# Roboteq_Board_V1_1.net
KiCad netlist of a schematic drawn in EAGLE
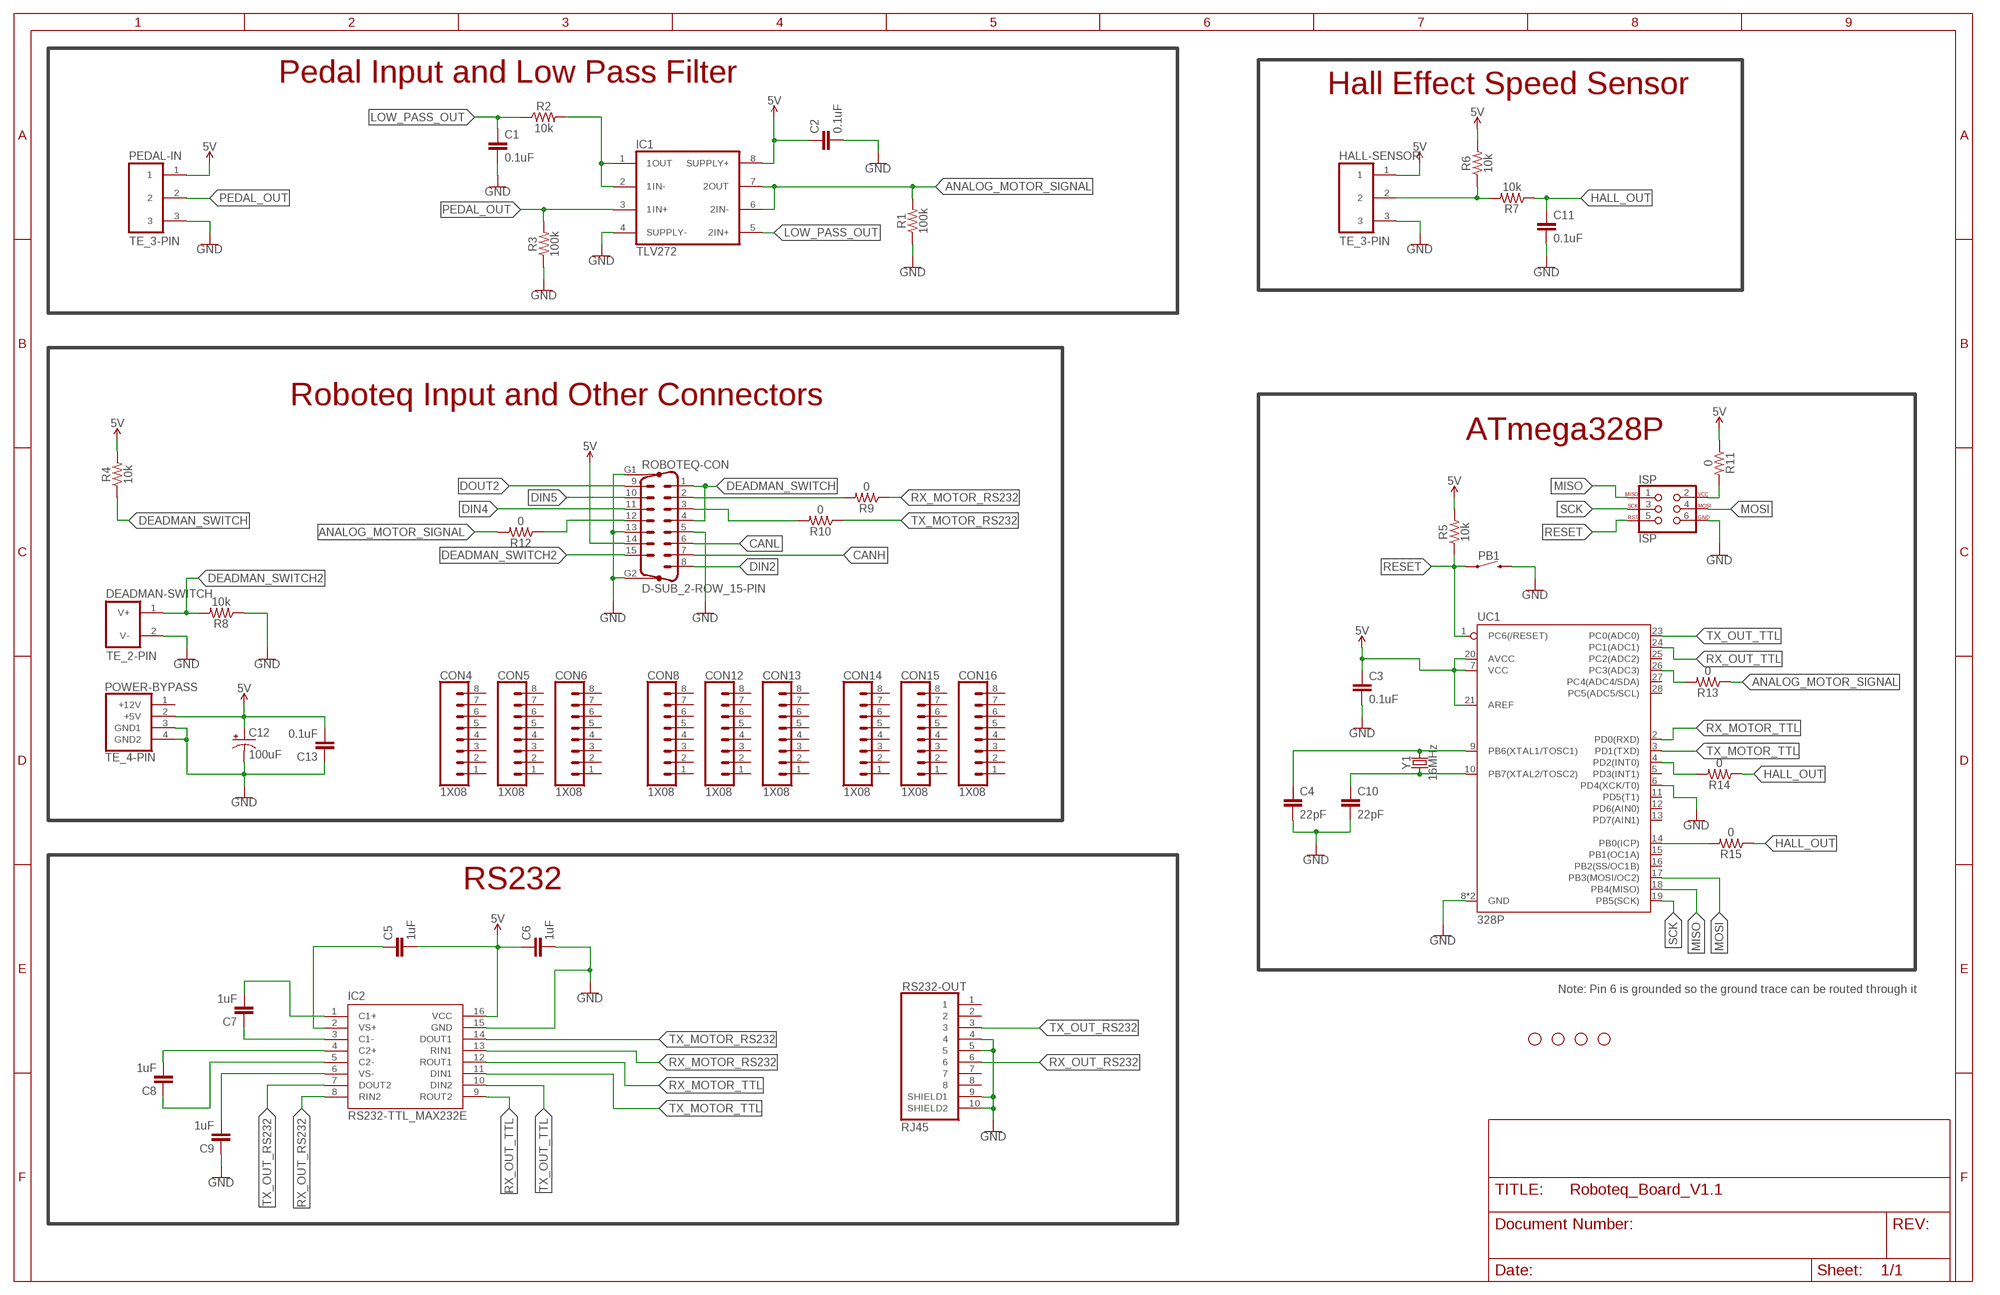
[diagram p0: schematic, sheet 1]

(export (version "E")
  (design (tool "Eeschema 10.0.6"))
  (components
    (comp (ref "C1")
      (value "0.1uF")
      (footprint "eagle-import:CAP-PTH-5MM")
      (libsource (lib "eagle-import") (part "CAPACITOR_CERAMIC_THROUGH-HOLE"))
    )
    (comp (ref "C2")
      (value "0.1uF")
      (footprint "eagle-import:CAP-PTH-5MM")
      (libsource (lib "eagle-import") (part "CAPACITOR_CERAMIC_THROUGH-HOLE"))
    )
    (comp (ref "C3")
      (value "0.1uF")
      (footprint "eagle-import:CAP-PTH-5MM")
      (libsource (lib "eagle-import") (part "CAPACITOR_CERAMIC_THROUGH-HOLE"))
    )
    (comp (ref "C4")
      (value "22pF")
      (footprint "eagle-import:CAP-PTH-5MM")
      (libsource (lib "eagle-import") (part "CAPACITOR_CERAMIC_THROUGH-HOLE"))
    )
    (comp (ref "C5")
      (value "1uF")
      (footprint "eagle-import:CAP-PTH-5MM")
      (libsource (lib "eagle-import") (part "CAPACITOR_CERAMIC_THROUGH-HOLE"))
    )
    (comp (ref "C6")
      (value "1uF")
      (footprint "eagle-import:CAP-PTH-5MM")
      (libsource (lib "eagle-import") (part "CAPACITOR_CERAMIC_THROUGH-HOLE"))
    )
    (comp (ref "C7")
      (value "1uF")
      (footprint "eagle-import:CAP-PTH-5MM")
      (libsource (lib "eagle-import") (part "CAPACITOR_CERAMIC_THROUGH-HOLE"))
    )
    (comp (ref "C8")
      (value "1uF")
      (footprint "eagle-import:CAP-PTH-5MM")
      (libsource (lib "eagle-import") (part "CAPACITOR_CERAMIC_THROUGH-HOLE"))
    )
    (comp (ref "C9")
      (value "1uF")
      (footprint "eagle-import:CAP-PTH-5MM")
      (libsource (lib "eagle-import") (part "CAPACITOR_CERAMIC_THROUGH-HOLE"))
    )
    (comp (ref "C10")
      (value "22pF")
      (footprint "eagle-import:CAP-PTH-5MM")
      (libsource (lib "eagle-import") (part "CAPACITOR_CERAMIC_THROUGH-HOLE"))
    )
    (comp (ref "C11")
      (value "0.1uF")
      (footprint "eagle-import:CAP-PTH-5MM")
      (libsource (lib "eagle-import") (part "CAPACITOR_CERAMIC_THROUGH-HOLE"))
    )
    (comp (ref "C12")
      (value "100uF")
      (footprint "eagle-import:CAPACITOR_100UF_50V")
      (libsource (lib "eagle-import") (part "CAPACITOR_ELECTROLYTIC_100UF"))
    )
    (comp (ref "C13")
      (value "0.1uF")
      (footprint "eagle-import:CAP-PTH-5MM")
      (libsource (lib "eagle-import") (part "CAPACITOR_CERAMIC_THROUGH-HOLE"))
    )
    (comp (ref "CON4")
      (value "1X08")
      (footprint "eagle-import:1X08")
      (libsource (lib "eagle-import") (part "1X08"))
    )
    (comp (ref "CON5")
      (value "1X08")
      (footprint "eagle-import:1X08")
      (libsource (lib "eagle-import") (part "1X08"))
    )
    (comp (ref "CON6")
      (value "1X08")
      (footprint "eagle-import:1X08")
      (libsource (lib "eagle-import") (part "1X08"))
    )
    (comp (ref "CON8")
      (value "1X08")
      (footprint "eagle-import:1X08")
      (libsource (lib "eagle-import") (part "1X08"))
    )
    (comp (ref "CON12")
      (value "1X08")
      (footprint "eagle-import:1X08")
      (libsource (lib "eagle-import") (part "1X08"))
    )
    (comp (ref "CON13")
      (value "1X08")
      (footprint "eagle-import:1X08")
      (libsource (lib "eagle-import") (part "1X08"))
    )
    (comp (ref "CON14")
      (value "1X08")
      (footprint "eagle-import:1X08")
      (libsource (lib "eagle-import") (part "1X08"))
    )
    (comp (ref "CON15")
      (value "1X08")
      (footprint "eagle-import:1X08")
      (libsource (lib "eagle-import") (part "1X08"))
    )
    (comp (ref "CON16")
      (value "1X08")
      (footprint "eagle-import:1X08")
      (libsource (lib "eagle-import") (part "1X08"))
    )
    (comp (ref "DEADMAN-SWITCH")
      (value "TE_2-PIN")
      (footprint "eagle-import:TE_2-PIN")
      (libsource (lib "eagle-import") (part "TE_2-PIN"))
    )
    (comp (ref "H1")
      (value "STAND-OFF")
      (footprint "eagle-import:STAND-OFF")
      (libsource (lib "eagle-import") (part "STAND-OFF"))
    )
    (comp (ref "H2")
      (value "STAND-OFF")
      (footprint "eagle-import:STAND-OFF")
      (libsource (lib "eagle-import") (part "STAND-OFF"))
    )
    (comp (ref "H3")
      (value "STAND-OFF")
      (footprint "eagle-import:STAND-OFF")
      (libsource (lib "eagle-import") (part "STAND-OFF"))
    )
    (comp (ref "H4")
      (value "STAND-OFF")
      (footprint "eagle-import:STAND-OFF")
      (libsource (lib "eagle-import") (part "STAND-OFF"))
    )
    (comp (ref "HALL-SENSOR")
      (value "TE_3-PIN")
      (footprint "eagle-import:TE_3-PIN")
      (libsource (lib "eagle-import") (part "TE_3-PIN"))
    )
    (comp (ref "IC1")
      (value "TLV272")
      (footprint "eagle-import:DIP08")
      (libsource (lib "eagle-import") (part "OP-AMP_DUAL"))
    )
    (comp (ref "IC2")
      (value "RS232-TTL_MAX232E")
      (footprint "eagle-import:DIP16")
      (libsource (lib "eagle-import") (part "RS232-TTL_MAX232E"))
    )
    (comp (ref "ISP")
      (value "ISP")
      (footprint "eagle-import:ISP_CONNECTOR")
      (libsource (lib "eagle-import") (part "ISP"))
    )
    (comp (ref "PB1")
      (value "PUSHBUTTON")
      (footprint "eagle-import:PUSHBUTTON")
      (libsource (lib "eagle-import") (part "PUSHBUTTON"))
    )
    (comp (ref "PEDAL-IN")
      (value "TE_3-PIN")
      (footprint "eagle-import:TE_3-PIN")
      (libsource (lib "eagle-import") (part "TE_3-PIN"))
    )
    (comp (ref "POWER-BYPASS")
      (value "TE_4-PIN")
      (footprint "eagle-import:TE_4-PIN")
      (libsource (lib "eagle-import") (part "TE_4-PIN"))
    )
    (comp (ref "R1")
      (value "100k")
      (footprint "eagle-import:AXIAL-0.3")
      (libsource (lib "eagle-import") (part "RESISTOR_THROUGH-HOLE_1/4W"))
    )
    (comp (ref "R2")
      (value "10k")
      (footprint "eagle-import:AXIAL-0.3")
      (libsource (lib "eagle-import") (part "RESISTOR_THROUGH-HOLE_1/4W"))
    )
    (comp (ref "R3")
      (value "100k")
      (footprint "eagle-import:AXIAL-0.3")
      (libsource (lib "eagle-import") (part "RESISTOR_THROUGH-HOLE_1/4W"))
    )
    (comp (ref "R4")
      (value "10k")
      (footprint "eagle-import:AXIAL-0.3")
      (libsource (lib "eagle-import") (part "RESISTOR_THROUGH-HOLE_1/4W"))
    )
    (comp (ref "R5")
      (value "10k")
      (footprint "eagle-import:AXIAL-0.3")
      (libsource (lib "eagle-import") (part "RESISTOR_THROUGH-HOLE_1/4W"))
    )
    (comp (ref "R6")
      (value "10k")
      (footprint "eagle-import:AXIAL-0.3")
      (libsource (lib "eagle-import") (part "RESISTOR_THROUGH-HOLE_1/4W"))
    )
    (comp (ref "R7")
      (value "10k")
      (footprint "eagle-import:AXIAL-0.3")
      (libsource (lib "eagle-import") (part "RESISTOR_THROUGH-HOLE_1/4W"))
    )
    (comp (ref "R8")
      (value "10k")
      (footprint "eagle-import:AXIAL-0.3")
      (libsource (lib "eagle-import") (part "RESISTOR_THROUGH-HOLE_1/4W"))
    )
    (comp (ref "R9")
      (value "0")
      (footprint "eagle-import:AXIAL-0.3")
      (libsource (lib "eagle-import") (part "RESISTOR_THROUGH-HOLE_1/4W"))
    )
    (comp (ref "R10")
      (value "0")
      (footprint "eagle-import:AXIAL-0.3")
      (libsource (lib "eagle-import") (part "RESISTOR_THROUGH-HOLE_1/4W"))
    )
    (comp (ref "R11")
      (value "0")
      (footprint "eagle-import:AXIAL-0.3")
      (libsource (lib "eagle-import") (part "RESISTOR_THROUGH-HOLE_1/4W"))
    )
    (comp (ref "R12")
      (value "0")
      (footprint "eagle-import:AXIAL-0.3")
      (libsource (lib "eagle-import") (part "RESISTOR_THROUGH-HOLE_1/4W"))
    )
    (comp (ref "R13")
      (value "0")
      (footprint "eagle-import:AXIAL-0.3")
      (libsource (lib "eagle-import") (part "RESISTOR_THROUGH-HOLE_1/4W"))
    )
    (comp (ref "R14")
      (value "0")
      (footprint "eagle-import:AXIAL-0.3")
      (libsource (lib "eagle-import") (part "RESISTOR_THROUGH-HOLE_1/4W"))
    )
    (comp (ref "R15")
      (value "0")
      (footprint "eagle-import:AXIAL-0.3")
      (libsource (lib "eagle-import") (part "RESISTOR_THROUGH-HOLE_1/4W"))
    )
    (comp (ref "ROBOTEQ-CON")
      (value "D-SUB_2-ROW_15-PIN")
      (footprint "eagle-import:D-SUB_2-ROW_15-PIN")
      (libsource (lib "eagle-import") (part "D-SUB_2-ROW_15-PIN"))
    )
    (comp (ref "RS232-OUT")
      (value "RJ45")
      (footprint "eagle-import:RJ45")
      (libsource (lib "eagle-import") (part "RJ45"))
    )
    (comp (ref "UC1")
      (value "328P")
      (footprint "eagle-import:DIP28")
      (libsource (lib "eagle-import") (part "ATMEGA328P_DIP28"))
    )
    (comp (ref "Y1")
      (value "16MHz")
      (footprint "eagle-import:HC49US")
      (libsource (lib "eagle-import") (part "CRYSTAL-16MHZPTH-HC49US"))
    )
  )
  (nets
    (net (code "1") (name "5V") (class "Default")
      (node (ref "C12") (pin "+") (pinfunction "+_+") (pintype "passive"))
      (node (ref "C13") (pin "2") (pinfunction "2_2") (pintype "passive"))
      (node (ref "C2") (pin "1") (pinfunction "1_1") (pintype "passive"))
      (node (ref "C3") (pin "1") (pinfunction "1_1") (pintype "passive"))
      (node (ref "C5") (pin "2") (pinfunction "2_2") (pintype "passive"))
      (node (ref "C6") (pin "1") (pinfunction "1_1") (pintype "passive"))
      (node (ref "HALL-SENSOR") (pin "1") (pinfunction "1_1") (pintype "passive"))
      (node (ref "IC1") (pin "8") (pinfunction "SUPPLY+_8") (pintype "bidirectional"))
      (node (ref "IC2") (pin "16") (pinfunction "VCC_16") (pintype "bidirectional"))
      (node (ref "PEDAL-IN") (pin "1") (pinfunction "1_1") (pintype "passive"))
      (node (ref "POWER-BYPASS") (pin "2") (pinfunction "+5V_2") (pintype "passive"))
      (node (ref "R11") (pin "P$1") (pinfunction "1_P$1") (pintype "passive"))
      (node (ref "R4") (pin "P$2") (pinfunction "2_P$2") (pintype "passive"))
      (node (ref "R5") (pin "P$2") (pinfunction "2_P$2") (pintype "passive"))
      (node (ref "R6") (pin "P$2") (pinfunction "2_P$2") (pintype "passive"))
      (node (ref "ROBOTEQ-CON") (pin "14") (pinfunction "14_14") (pintype "passive"))
      (node (ref "UC1") (pin "20") (pinfunction "AVCC_20") (pintype "bidirectional"))
      (node (ref "UC1") (pin "21") (pinfunction "AREF_21") (pintype "bidirectional"))
      (node (ref "UC1") (pin "7") (pinfunction "VCC_7") (pintype "bidirectional"))
    )
    (net (code "2") (name "ANALOG_MOTOR_SIGNAL") (class "Default")
      (node (ref "IC1") (pin "6") (pinfunction "2IN-_6") (pintype "bidirectional"))
      (node (ref "IC1") (pin "7") (pinfunction "2OUT_7") (pintype "bidirectional"))
      (node (ref "R1") (pin "P$2") (pinfunction "2_P$2") (pintype "passive"))
      (node (ref "R12") (pin "P$2") (pinfunction "2_P$2") (pintype "passive"))
      (node (ref "R13") (pin "P$1") (pinfunction "1_P$1") (pintype "passive"))
    )
    (net (code "3") (name "CANH") (class "Default")
      (node (ref "ROBOTEQ-CON") (pin "7") (pinfunction "7_7") (pintype "passive"))
    )
    (net (code "4") (name "CANL") (class "Default")
      (node (ref "ROBOTEQ-CON") (pin "6") (pinfunction "6_6") (pintype "passive"))
    )
    (net (code "5") (name "DEADMAN_SWITCH") (class "Default")
      (node (ref "R4") (pin "P$1") (pinfunction "1_P$1") (pintype "passive"))
      (node (ref "ROBOTEQ-CON") (pin "1") (pinfunction "1_1") (pintype "passive"))
      (node (ref "ROBOTEQ-CON") (pin "4") (pinfunction "4_4") (pintype "passive"))
    )
    (net (code "6") (name "DEADMAN_SWITCH2") (class "Default")
      (node (ref "DEADMAN-SWITCH") (pin "1") (pinfunction "V+_1") (pintype "passive"))
      (node (ref "R8") (pin "P$2") (pinfunction "2_P$2") (pintype "passive"))
      (node (ref "ROBOTEQ-CON") (pin "15") (pinfunction "15_15") (pintype "passive"))
    )
    (net (code "7") (name "DIN2") (class "Default")
      (node (ref "ROBOTEQ-CON") (pin "8") (pinfunction "8_8") (pintype "passive"))
    )
    (net (code "8") (name "DIN4") (class "Default")
      (node (ref "ROBOTEQ-CON") (pin "11") (pinfunction "11_11") (pintype "passive"))
    )
    (net (code "9") (name "DIN5") (class "Default")
      (node (ref "ROBOTEQ-CON") (pin "10") (pinfunction "10_10") (pintype "passive"))
    )
    (net (code "10") (name "DOUT2") (class "Default")
      (node (ref "ROBOTEQ-CON") (pin "9") (pinfunction "9_9") (pintype "passive"))
    )
    (net (code "11") (name "GND") (class "Default")
      (node (ref "C1") (pin "2") (pinfunction "2_2") (pintype "passive"))
      (node (ref "C10") (pin "2") (pinfunction "2_2") (pintype "passive"))
      (node (ref "C11") (pin "2") (pinfunction "2_2") (pintype "passive"))
      (node (ref "C12") (pin "-") (pinfunction "-_-") (pintype "passive"))
      (node (ref "C13") (pin "1") (pinfunction "1_1") (pintype "passive"))
      (node (ref "C2") (pin "2") (pinfunction "2_2") (pintype "passive"))
      (node (ref "C3") (pin "2") (pinfunction "2_2") (pintype "passive"))
      (node (ref "C4") (pin "2") (pinfunction "2_2") (pintype "passive"))
      (node (ref "C6") (pin "2") (pinfunction "2_2") (pintype "passive"))
      (node (ref "C9") (pin "1") (pinfunction "1_1") (pintype "passive"))
      (node (ref "DEADMAN-SWITCH") (pin "2") (pinfunction "V-_2") (pintype "passive"))
      (node (ref "HALL-SENSOR") (pin "3") (pinfunction "3_3") (pintype "passive"))
      (node (ref "IC1") (pin "4") (pinfunction "SUPPLY-_4") (pintype "bidirectional"))
      (node (ref "IC2") (pin "15") (pinfunction "GND_15") (pintype "bidirectional"))
      (node (ref "ISP") (pin "6") (pinfunction "6_6") (pintype "passive"))
      (node (ref "PB1") (pin "3") (pinfunction "2_3") (pintype "passive"))
      (node (ref "PB1") (pin "4") (pinfunction "2_4") (pintype "passive"))
      (node (ref "PEDAL-IN") (pin "3") (pinfunction "3_3") (pintype "passive"))
      (node (ref "POWER-BYPASS") (pin "3") (pinfunction "GND1_3") (pintype "passive"))
      (node (ref "POWER-BYPASS") (pin "4") (pinfunction "GND2_4") (pintype "passive"))
      (node (ref "R1") (pin "P$1") (pinfunction "1_P$1") (pintype "passive"))
      (node (ref "R3") (pin "P$1") (pinfunction "1_P$1") (pintype "passive"))
      (node (ref "R8") (pin "P$1") (pinfunction "1_P$1") (pintype "passive"))
      (node (ref "ROBOTEQ-CON") (pin "13") (pinfunction "13_13") (pintype "passive"))
      (node (ref "ROBOTEQ-CON") (pin "5") (pinfunction "5_5") (pintype "passive"))
      (node (ref "ROBOTEQ-CON") (pin "G1") (pinfunction "GND1_G1") (pintype "passive"))
      (node (ref "ROBOTEQ-CON") (pin "G2") (pinfunction "GND2_G2") (pintype "passive"))
      (node (ref "RS232-OUT") (pin "10") (pinfunction "SHIELD2_10") (pintype "passive"))
      (node (ref "RS232-OUT") (pin "4") (pinfunction "4_4") (pintype "passive"))
      (node (ref "RS232-OUT") (pin "5") (pinfunction "5_5") (pintype "passive"))
      (node (ref "RS232-OUT") (pin "9") (pinfunction "SHIELD1_9") (pintype "passive"))
      (node (ref "UC1") (pin "22") (pinfunction "GND_22") (pintype "bidirectional"))
      (node (ref "UC1") (pin "6") (pinfunction "PD4(XCK/T0)_6") (pintype "bidirectional"))
      (node (ref "UC1") (pin "8") (pinfunction "GND_8") (pintype "bidirectional"))
    )
    (net (code "12") (name "HALL_OUT") (class "Default")
      (node (ref "C11") (pin "1") (pinfunction "1_1") (pintype "passive"))
      (node (ref "R14") (pin "P$1") (pinfunction "1_P$1") (pintype "passive"))
      (node (ref "R15") (pin "P$1") (pinfunction "1_P$1") (pintype "passive"))
      (node (ref "R7") (pin "P$1") (pinfunction "1_P$1") (pintype "passive"))
    )
    (net (code "13") (name "LOW_PASS_OUT") (class "Default")
      (node (ref "C1") (pin "1") (pinfunction "1_1") (pintype "passive"))
      (node (ref "IC1") (pin "5") (pinfunction "2IN+_5") (pintype "bidirectional"))
      (node (ref "R2") (pin "P$1") (pinfunction "1_P$1") (pintype "passive"))
    )
    (net (code "14") (name "MISO") (class "Default")
      (node (ref "ISP") (pin "1") (pinfunction "1_1") (pintype "passive"))
      (node (ref "UC1") (pin "18") (pinfunction "PB4(MISO)_18") (pintype "bidirectional"))
    )
    (net (code "15") (name "MOSI") (class "Default")
      (node (ref "ISP") (pin "4") (pinfunction "4_4") (pintype "passive"))
      (node (ref "UC1") (pin "17") (pinfunction "PB3(MOSI/OC2)_17") (pintype "bidirectional"))
    )
    (net (code "16") (name "Net-(IC1-1IN-)") (class "Default")
      (node (ref "IC1") (pin "1") (pinfunction "1OUT_1") (pintype "bidirectional"))
      (node (ref "IC1") (pin "2") (pinfunction "1IN-_2") (pintype "bidirectional"))
      (node (ref "R2") (pin "P$2") (pinfunction "2_P$2") (pintype "passive"))
    )
    (net (code "17") (name "Net-(IC2-C1+)") (class "Default")
      (node (ref "C7") (pin "2") (pinfunction "2_2") (pintype "passive"))
      (node (ref "IC2") (pin "1") (pinfunction "C1+_1") (pintype "bidirectional"))
    )
    (net (code "18") (name "Net-(IC2-C1-)") (class "Default")
      (node (ref "C7") (pin "1") (pinfunction "1_1") (pintype "passive"))
      (node (ref "IC2") (pin "3") (pinfunction "C1-_3") (pintype "bidirectional"))
    )
    (net (code "19") (name "Net-(IC2-C2+)") (class "Default")
      (node (ref "C8") (pin "2") (pinfunction "2_2") (pintype "passive"))
      (node (ref "IC2") (pin "4") (pinfunction "C2+_4") (pintype "bidirectional"))
    )
    (net (code "20") (name "Net-(IC2-C2-)") (class "Default")
      (node (ref "C8") (pin "1") (pinfunction "1_1") (pintype "passive"))
      (node (ref "IC2") (pin "5") (pinfunction "C2-_5") (pintype "bidirectional"))
    )
    (net (code "21") (name "Net-(IC2-VS+)") (class "Default")
      (node (ref "C5") (pin "1") (pinfunction "1_1") (pintype "passive"))
      (node (ref "IC2") (pin "2") (pinfunction "VS+_2") (pintype "bidirectional"))
    )
    (net (code "22") (name "Net-(IC2-VS-)") (class "Default")
      (node (ref "C9") (pin "2") (pinfunction "2_2") (pintype "passive"))
      (node (ref "IC2") (pin "6") (pinfunction "VS-_6") (pintype "bidirectional"))
    )
    (net (code "23") (name "Net-(R6-1)") (class "Default")
      (node (ref "HALL-SENSOR") (pin "2") (pinfunction "2_2") (pintype "passive"))
      (node (ref "R6") (pin "P$1") (pinfunction "1_P$1") (pintype "passive"))
      (node (ref "R7") (pin "P$2") (pinfunction "2_P$2") (pintype "passive"))
    )
    (net (code "24") (name "Net-(R9-2)") (class "Default")
      (node (ref "R9") (pin "P$2") (pinfunction "2_P$2") (pintype "passive"))
      (node (ref "ROBOTEQ-CON") (pin "2") (pinfunction "2_2") (pintype "passive"))
    )
    (net (code "25") (name "Net-(R10-2)") (class "Default")
      (node (ref "R10") (pin "P$2") (pinfunction "2_P$2") (pintype "passive"))
      (node (ref "ROBOTEQ-CON") (pin "3") (pinfunction "3_3") (pintype "passive"))
    )
    (net (code "26") (name "Net-(R11-2)") (class "Default")
      (node (ref "ISP") (pin "2") (pinfunction "2_2") (pintype "passive"))
      (node (ref "R11") (pin "P$2") (pinfunction "2_P$2") (pintype "passive"))
    )
    (net (code "27") (name "Net-(R12-1)") (class "Default")
      (node (ref "R12") (pin "P$1") (pinfunction "1_P$1") (pintype "passive"))
      (node (ref "ROBOTEQ-CON") (pin "12") (pinfunction "12_12") (pintype "passive"))
    )
    (net (code "28") (name "Net-(R13-2)") (class "Default")
      (node (ref "R13") (pin "P$2") (pinfunction "2_P$2") (pintype "passive"))
      (node (ref "UC1") (pin "26") (pinfunction "PC3(ADC3)_26") (pintype "bidirectional"))
    )
    (net (code "29") (name "Net-(R14-2)") (class "Default")
      (node (ref "R14") (pin "P$2") (pinfunction "2_P$2") (pintype "passive"))
      (node (ref "UC1") (pin "4") (pinfunction "PD2(INT0)_4") (pintype "bidirectional"))
    )
    (net (code "30") (name "Net-(R15-2)") (class "Default")
      (node (ref "R15") (pin "P$2") (pinfunction "2_P$2") (pintype "passive"))
      (node (ref "UC1") (pin "14") (pinfunction "PB0(ICP)_14") (pintype "bidirectional"))
    )
    (net (code "31") (name "Net-(UC1-PB6(XTAL1{slash}TOSC1))") (class "Default")
      (node (ref "C4") (pin "1") (pinfunction "1_1") (pintype "passive"))
      (node (ref "UC1") (pin "9") (pinfunction "PB6(XTAL1/TOSC1)_9") (pintype "bidirectional"))
      (node (ref "Y1") (pin "2") (pinfunction "2_2") (pintype "passive"))
    )
    (net (code "32") (name "Net-(UC1-PB7(XTAL2{slash}TOSC2))") (class "Default")
      (node (ref "C10") (pin "1") (pinfunction "1_1") (pintype "passive"))
      (node (ref "UC1") (pin "10") (pinfunction "PB7(XTAL2/TOSC2)_10") (pintype "bidirectional"))
      (node (ref "Y1") (pin "1") (pinfunction "1_1") (pintype "passive"))
    )
    (net (code "33") (name "PEDAL_OUT") (class "Default")
      (node (ref "IC1") (pin "3") (pinfunction "1IN+_3") (pintype "bidirectional"))
      (node (ref "PEDAL-IN") (pin "2") (pinfunction "2_2") (pintype "passive"))
      (node (ref "R3") (pin "P$2") (pinfunction "2_P$2") (pintype "passive"))
    )
    (net (code "34") (name "RESET") (class "Default")
      (node (ref "ISP") (pin "5") (pinfunction "5_5") (pintype "passive"))
      (node (ref "PB1") (pin "1") (pinfunction "1_1") (pintype "passive"))
      (node (ref "PB1") (pin "2") (pinfunction "1_2") (pintype "passive"))
      (node (ref "R5") (pin "P$1") (pinfunction "1_P$1") (pintype "passive"))
      (node (ref "UC1") (pin "1") (pinfunction "PC6(/RESET)_1") (pintype "bidirectional"))
    )
    (net (code "35") (name "RX_MOTOR_RS232") (class "Default")
      (node (ref "IC2") (pin "13") (pinfunction "RIN1_13") (pintype "bidirectional"))
      (node (ref "R9") (pin "P$1") (pinfunction "1_P$1") (pintype "passive"))
    )
    (net (code "36") (name "RX_MOTOR_TTL") (class "Default")
      (node (ref "IC2") (pin "12") (pinfunction "ROUT1_12") (pintype "bidirectional"))
      (node (ref "UC1") (pin "2") (pinfunction "PD0(RXD)_2") (pintype "bidirectional"))
    )
    (net (code "37") (name "RX_OUT_RS232") (class "Default")
      (node (ref "IC2") (pin "8") (pinfunction "RIN2_8") (pintype "bidirectional"))
      (node (ref "RS232-OUT") (pin "6") (pinfunction "6_6") (pintype "passive"))
    )
    (net (code "38") (name "RX_OUT_TTL") (class "Default")
      (node (ref "IC2") (pin "9") (pinfunction "ROUT2_9") (pintype "bidirectional"))
      (node (ref "UC1") (pin "24") (pinfunction "PC1(ADC1)_24") (pintype "bidirectional"))
    )
    (net (code "39") (name "SCK") (class "Default")
      (node (ref "ISP") (pin "3") (pinfunction "3_3") (pintype "passive"))
      (node (ref "UC1") (pin "19") (pinfunction "PB5(SCK)_19") (pintype "bidirectional"))
    )
    (net (code "40") (name "TX_MOTOR_RS232") (class "Default")
      (node (ref "IC2") (pin "14") (pinfunction "DOUT1_14") (pintype "bidirectional"))
      (node (ref "R10") (pin "P$1") (pinfunction "1_P$1") (pintype "passive"))
    )
    (net (code "41") (name "TX_MOTOR_TTL") (class "Default")
      (node (ref "IC2") (pin "11") (pinfunction "DIN1_11") (pintype "bidirectional"))
      (node (ref "UC1") (pin "3") (pinfunction "PD1(TXD)_3") (pintype "bidirectional"))
    )
    (net (code "42") (name "TX_OUT_RS232") (class "Default")
      (node (ref "IC2") (pin "7") (pinfunction "DOUT2_7") (pintype "bidirectional"))
      (node (ref "RS232-OUT") (pin "3") (pinfunction "3_3") (pintype "passive"))
    )
    (net (code "43") (name "TX_OUT_TTL") (class "Default")
      (node (ref "IC2") (pin "10") (pinfunction "DIN2_10") (pintype "bidirectional"))
      (node (ref "UC1") (pin "23") (pinfunction "PC0(ADC0)_23") (pintype "bidirectional"))
    )
    (net (code "44") (name "unconnected-(CON4-Pad1)") (class "Default")
      (node (ref "CON4") (pin "1") (pinfunction "1_1") (pintype "passive"))
    )
    (net (code "45") (name "unconnected-(CON4-Pad2)") (class "Default")
      (node (ref "CON4") (pin "2") (pinfunction "2_2") (pintype "passive"))
    )
    (net (code "46") (name "unconnected-(CON4-Pad3)") (class "Default")
      (node (ref "CON4") (pin "3") (pinfunction "3_3") (pintype "passive"))
    )
    (net (code "47") (name "unconnected-(CON4-Pad4)") (class "Default")
      (node (ref "CON4") (pin "4") (pinfunction "4_4") (pintype "passive"))
    )
    (net (code "48") (name "unconnected-(CON4-Pad5)") (class "Default")
      (node (ref "CON4") (pin "5") (pinfunction "5_5") (pintype "passive"))
    )
    (net (code "49") (name "unconnected-(CON4-Pad6)") (class "Default")
      (node (ref "CON4") (pin "6") (pinfunction "6_6") (pintype "passive"))
    )
    (net (code "50") (name "unconnected-(CON4-Pad7)") (class "Default")
      (node (ref "CON4") (pin "7") (pinfunction "7_7") (pintype "passive"))
    )
    (net (code "51") (name "unconnected-(CON4-Pad8)") (class "Default")
      (node (ref "CON4") (pin "8") (pinfunction "8_8") (pintype "passive"))
    )
    (net (code "52") (name "unconnected-(CON5-Pad1)") (class "Default")
      (node (ref "CON5") (pin "1") (pinfunction "1_1") (pintype "passive"))
    )
    (net (code "53") (name "unconnected-(CON5-Pad2)") (class "Default")
      (node (ref "CON5") (pin "2") (pinfunction "2_2") (pintype "passive"))
    )
    (net (code "54") (name "unconnected-(CON5-Pad3)") (class "Default")
      (node (ref "CON5") (pin "3") (pinfunction "3_3") (pintype "passive"))
    )
    (net (code "55") (name "unconnected-(CON5-Pad4)") (class "Default")
      (node (ref "CON5") (pin "4") (pinfunction "4_4") (pintype "passive"))
    )
    (net (code "56") (name "unconnected-(CON5-Pad5)") (class "Default")
      (node (ref "CON5") (pin "5") (pinfunction "5_5") (pintype "passive"))
    )
    (net (code "57") (name "unconnected-(CON5-Pad6)") (class "Default")
      (node (ref "CON5") (pin "6") (pinfunction "6_6") (pintype "passive"))
    )
    (net (code "58") (name "unconnected-(CON5-Pad7)") (class "Default")
      (node (ref "CON5") (pin "7") (pinfunction "7_7") (pintype "passive"))
    )
    (net (code "59") (name "unconnected-(CON5-Pad8)") (class "Default")
      (node (ref "CON5") (pin "8") (pinfunction "8_8") (pintype "passive"))
    )
    (net (code "60") (name "unconnected-(CON6-Pad1)") (class "Default")
      (node (ref "CON6") (pin "1") (pinfunction "1_1") (pintype "passive"))
    )
    (net (code "61") (name "unconnected-(CON6-Pad2)") (class "Default")
      (node (ref "CON6") (pin "2") (pinfunction "2_2") (pintype "passive"))
    )
    (net (code "62") (name "unconnected-(CON6-Pad3)") (class "Default")
      (node (ref "CON6") (pin "3") (pinfunction "3_3") (pintype "passive"))
    )
    (net (code "63") (name "unconnected-(CON6-Pad4)") (class "Default")
      (node (ref "CON6") (pin "4") (pinfunction "4_4") (pintype "passive"))
    )
    (net (code "64") (name "unconnected-(CON6-Pad5)") (class "Default")
      (node (ref "CON6") (pin "5") (pinfunction "5_5") (pintype "passive"))
    )
    (net (code "65") (name "unconnected-(CON6-Pad6)") (class "Default")
      (node (ref "CON6") (pin "6") (pinfunction "6_6") (pintype "passive"))
    )
    (net (code "66") (name "unconnected-(CON6-Pad7)") (class "Default")
      (node (ref "CON6") (pin "7") (pinfunction "7_7") (pintype "passive"))
    )
    (net (code "67") (name "unconnected-(CON6-Pad8)") (class "Default")
      (node (ref "CON6") (pin "8") (pinfunction "8_8") (pintype "passive"))
    )
    (net (code "68") (name "unconnected-(CON8-Pad1)") (class "Default")
      (node (ref "CON8") (pin "1") (pinfunction "1_1") (pintype "passive"))
    )
    (net (code "69") (name "unconnected-(CON8-Pad2)") (class "Default")
      (node (ref "CON8") (pin "2") (pinfunction "2_2") (pintype "passive"))
    )
    (net (code "70") (name "unconnected-(CON8-Pad3)") (class "Default")
      (node (ref "CON8") (pin "3") (pinfunction "3_3") (pintype "passive"))
    )
    (net (code "71") (name "unconnected-(CON8-Pad4)") (class "Default")
      (node (ref "CON8") (pin "4") (pinfunction "4_4") (pintype "passive"))
    )
    (net (code "72") (name "unconnected-(CON8-Pad5)") (class "Default")
      (node (ref "CON8") (pin "5") (pinfunction "5_5") (pintype "passive"))
    )
    (net (code "73") (name "unconnected-(CON8-Pad6)") (class "Default")
      (node (ref "CON8") (pin "6") (pinfunction "6_6") (pintype "passive"))
    )
    (net (code "74") (name "unconnected-(CON8-Pad7)") (class "Default")
      (node (ref "CON8") (pin "7") (pinfunction "7_7") (pintype "passive"))
    )
    (net (code "75") (name "unconnected-(CON8-Pad8)") (class "Default")
      (node (ref "CON8") (pin "8") (pinfunction "8_8") (pintype "passive"))
    )
    (net (code "76") (name "unconnected-(CON12-Pad1)") (class "Default")
      (node (ref "CON12") (pin "1") (pinfunction "1_1") (pintype "passive"))
    )
    (net (code "77") (name "unconnected-(CON12-Pad2)") (class "Default")
      (node (ref "CON12") (pin "2") (pinfunction "2_2") (pintype "passive"))
    )
    (net (code "78") (name "unconnected-(CON12-Pad3)") (class "Default")
      (node (ref "CON12") (pin "3") (pinfunction "3_3") (pintype "passive"))
    )
    (net (code "79") (name "unconnected-(CON12-Pad4)") (class "Default")
      (node (ref "CON12") (pin "4") (pinfunction "4_4") (pintype "passive"))
    )
    (net (code "80") (name "unconnected-(CON12-Pad5)") (class "Default")
      (node (ref "CON12") (pin "5") (pinfunction "5_5") (pintype "passive"))
    )
    (net (code "81") (name "unconnected-(CON12-Pad6)") (class "Default")
      (node (ref "CON12") (pin "6") (pinfunction "6_6") (pintype "passive"))
    )
    (net (code "82") (name "unconnected-(CON12-Pad7)") (class "Default")
      (node (ref "CON12") (pin "7") (pinfunction "7_7") (pintype "passive"))
    )
    (net (code "83") (name "unconnected-(CON12-Pad8)") (class "Default")
      (node (ref "CON12") (pin "8") (pinfunction "8_8") (pintype "passive"))
    )
    (net (code "84") (name "unconnected-(CON13-Pad1)") (class "Default")
      (node (ref "CON13") (pin "1") (pinfunction "1_1") (pintype "passive"))
    )
    (net (code "85") (name "unconnected-(CON13-Pad2)") (class "Default")
      (node (ref "CON13") (pin "2") (pinfunction "2_2") (pintype "passive"))
    )
    (net (code "86") (name "unconnected-(CON13-Pad3)") (class "Default")
      (node (ref "CON13") (pin "3") (pinfunction "3_3") (pintype "passive"))
    )
    (net (code "87") (name "unconnected-(CON13-Pad4)") (class "Default")
      (node (ref "CON13") (pin "4") (pinfunction "4_4") (pintype "passive"))
    )
    (net (code "88") (name "unconnected-(CON13-Pad5)") (class "Default")
      (node (ref "CON13") (pin "5") (pinfunction "5_5") (pintype "passive"))
    )
    (net (code "89") (name "unconnected-(CON13-Pad6)") (class "Default")
      (node (ref "CON13") (pin "6") (pinfunction "6_6") (pintype "passive"))
    )
    (net (code "90") (name "unconnected-(CON13-Pad7)") (class "Default")
      (node (ref "CON13") (pin "7") (pinfunction "7_7") (pintype "passive"))
    )
    (net (code "91") (name "unconnected-(CON13-Pad8)") (class "Default")
      (node (ref "CON13") (pin "8") (pinfunction "8_8") (pintype "passive"))
    )
    (net (code "92") (name "unconnected-(CON14-Pad1)") (class "Default")
      (node (ref "CON14") (pin "1") (pinfunction "1_1") (pintype "passive"))
    )
    (net (code "93") (name "unconnected-(CON14-Pad2)") (class "Default")
      (node (ref "CON14") (pin "2") (pinfunction "2_2") (pintype "passive"))
    )
    (net (code "94") (name "unconnected-(CON14-Pad3)") (class "Default")
      (node (ref "CON14") (pin "3") (pinfunction "3_3") (pintype "passive"))
    )
    (net (code "95") (name "unconnected-(CON14-Pad4)") (class "Default")
      (node (ref "CON14") (pin "4") (pinfunction "4_4") (pintype "passive"))
    )
    (net (code "96") (name "unconnected-(CON14-Pad5)") (class "Default")
      (node (ref "CON14") (pin "5") (pinfunction "5_5") (pintype "passive"))
    )
    (net (code "97") (name "unconnected-(CON14-Pad6)") (class "Default")
      (node (ref "CON14") (pin "6") (pinfunction "6_6") (pintype "passive"))
    )
    (net (code "98") (name "unconnected-(CON14-Pad7)") (class "Default")
      (node (ref "CON14") (pin "7") (pinfunction "7_7") (pintype "passive"))
    )
    (net (code "99") (name "unconnected-(CON14-Pad8)") (class "Default")
      (node (ref "CON14") (pin "8") (pinfunction "8_8") (pintype "passive"))
    )
    (net (code "100") (name "unconnected-(CON15-Pad1)") (class "Default")
      (node (ref "CON15") (pin "1") (pinfunction "1_1") (pintype "passive"))
    )
    (net (code "101") (name "unconnected-(CON15-Pad2)") (class "Default")
      (node (ref "CON15") (pin "2") (pinfunction "2_2") (pintype "passive"))
    )
    (net (code "102") (name "unconnected-(CON15-Pad3)") (class "Default")
      (node (ref "CON15") (pin "3") (pinfunction "3_3") (pintype "passive"))
    )
    (net (code "103") (name "unconnected-(CON15-Pad4)") (class "Default")
      (node (ref "CON15") (pin "4") (pinfunction "4_4") (pintype "passive"))
    )
    (net (code "104") (name "unconnected-(CON15-Pad5)") (class "Default")
      (node (ref "CON15") (pin "5") (pinfunction "5_5") (pintype "passive"))
    )
    (net (code "105") (name "unconnected-(CON15-Pad6)") (class "Default")
      (node (ref "CON15") (pin "6") (pinfunction "6_6") (pintype "passive"))
    )
    (net (code "106") (name "unconnected-(CON15-Pad7)") (class "Default")
      (node (ref "CON15") (pin "7") (pinfunction "7_7") (pintype "passive"))
    )
    (net (code "107") (name "unconnected-(CON15-Pad8)") (class "Default")
      (node (ref "CON15") (pin "8") (pinfunction "8_8") (pintype "passive"))
    )
    (net (code "108") (name "unconnected-(CON16-Pad1)") (class "Default")
      (node (ref "CON16") (pin "1") (pinfunction "1_1") (pintype "passive"))
    )
    (net (code "109") (name "unconnected-(CON16-Pad2)") (class "Default")
      (node (ref "CON16") (pin "2") (pinfunction "2_2") (pintype "passive"))
    )
    (net (code "110") (name "unconnected-(CON16-Pad3)") (class "Default")
      (node (ref "CON16") (pin "3") (pinfunction "3_3") (pintype "passive"))
    )
    (net (code "111") (name "unconnected-(CON16-Pad4)") (class "Default")
      (node (ref "CON16") (pin "4") (pinfunction "4_4") (pintype "passive"))
    )
    (net (code "112") (name "unconnected-(CON16-Pad5)") (class "Default")
      (node (ref "CON16") (pin "5") (pinfunction "5_5") (pintype "passive"))
    )
    (net (code "113") (name "unconnected-(CON16-Pad6)") (class "Default")
      (node (ref "CON16") (pin "6") (pinfunction "6_6") (pintype "passive"))
    )
    (net (code "114") (name "unconnected-(CON16-Pad7)") (class "Default")
      (node (ref "CON16") (pin "7") (pinfunction "7_7") (pintype "passive"))
    )
    (net (code "115") (name "unconnected-(CON16-Pad8)") (class "Default")
      (node (ref "CON16") (pin "8") (pinfunction "8_8") (pintype "passive"))
    )
    (net (code "116") (name "unconnected-(POWER-BYPASS-+12V-Pad1)") (class "Default")
      (node (ref "POWER-BYPASS") (pin "1") (pinfunction "+12V_1") (pintype "passive"))
    )
    (net (code "117") (name "unconnected-(RS232-OUT-Pad1)") (class "Default")
      (node (ref "RS232-OUT") (pin "1") (pinfunction "1_1") (pintype "passive"))
    )
    (net (code "118") (name "unconnected-(RS232-OUT-Pad2)") (class "Default")
      (node (ref "RS232-OUT") (pin "2") (pinfunction "2_2") (pintype "passive"))
    )
    (net (code "119") (name "unconnected-(RS232-OUT-Pad7)") (class "Default")
      (node (ref "RS232-OUT") (pin "7") (pinfunction "7_7") (pintype "passive"))
    )
    (net (code "120") (name "unconnected-(RS232-OUT-Pad8)") (class "Default")
      (node (ref "RS232-OUT") (pin "8") (pinfunction "8_8") (pintype "passive"))
    )
    (net (code "121") (name "unconnected-(UC1-PB1(OC1A)-Pad15)") (class "Default")
      (node (ref "UC1") (pin "15") (pinfunction "PB1(OC1A)_15") (pintype "bidirectional"))
    )
    (net (code "122") (name "unconnected-(UC1-PB2(SS{slash}OC1B)-Pad16)") (class "Default")
      (node (ref "UC1") (pin "16") (pinfunction "PB2(SS/OC1B)_16") (pintype "bidirectional"))
    )
    (net (code "123") (name "unconnected-(UC1-PC2(ADC2)-Pad25)") (class "Default")
      (node (ref "UC1") (pin "25") (pinfunction "PC2(ADC2)_25") (pintype "bidirectional"))
    )
    (net (code "124") (name "unconnected-(UC1-PC4(ADC4{slash}SDA)-Pad27)") (class "Default")
      (node (ref "UC1") (pin "27") (pinfunction "PC4(ADC4/SDA)_27") (pintype "bidirectional"))
    )
    (net (code "125") (name "unconnected-(UC1-PC5(ADC5{slash}SCL)-Pad28)") (class "Default")
      (node (ref "UC1") (pin "28") (pinfunction "PC5(ADC5/SCL)_28") (pintype "bidirectional"))
    )
    (net (code "126") (name "unconnected-(UC1-PD3(INT1)-Pad5)") (class "Default")
      (node (ref "UC1") (pin "5") (pinfunction "PD3(INT1)_5") (pintype "bidirectional"))
    )
    (net (code "127") (name "unconnected-(UC1-PD5(T1)-Pad11)") (class "Default")
      (node (ref "UC1") (pin "11") (pinfunction "PD5(T1)_11") (pintype "bidirectional"))
    )
    (net (code "128") (name "unconnected-(UC1-PD6(AIN0)-Pad12)") (class "Default")
      (node (ref "UC1") (pin "12") (pinfunction "PD6(AIN0)_12") (pintype "bidirectional"))
    )
    (net (code "129") (name "unconnected-(UC1-PD7(AIN1)-Pad13)") (class "Default")
      (node (ref "UC1") (pin "13") (pinfunction "PD7(AIN1)_13") (pintype "bidirectional"))
    )
  )
)
